# Final_circuit.net
KiCad netlist of a schematic drawn in EAGLE
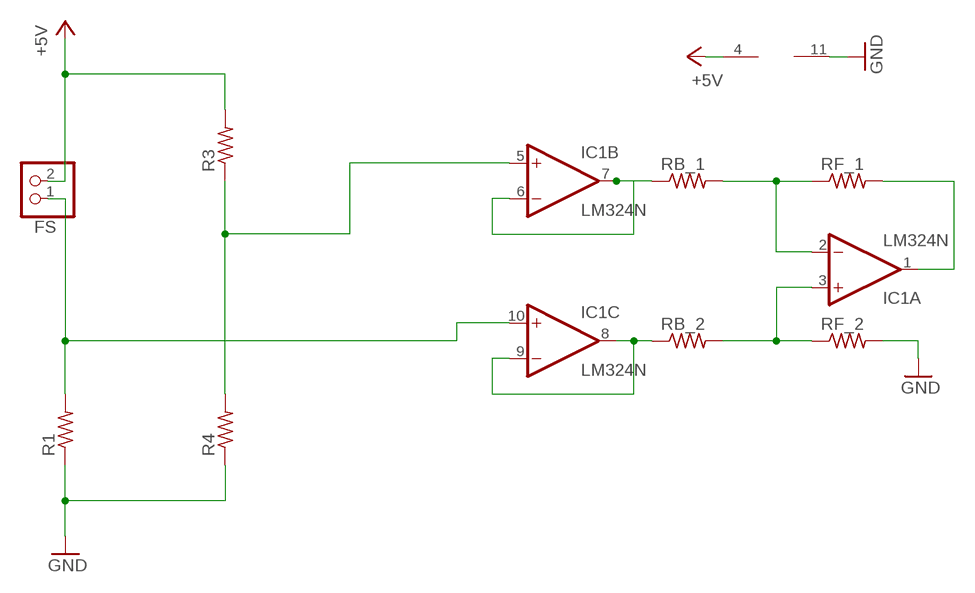
[diagram p0: schematic, sheet 1]

(export (version "E")
  (design (tool "Eeschema 10.0.6"))
  (components
    (comp (ref "FS")
      (value "PINHD-1X2")
      (footprint "eagle-import:1X02")
      (libsource (lib "eagle-import") (part "PINHD-1X2"))
    )
    (comp (ref "IC1")
      (value "LM324N")
      (footprint "eagle-import:DIL14")
      (libsource (lib "eagle-import") (part "LM324N"))
    )
    (comp (ref "R1")
      (value "R-US_0207/10")
      (footprint "eagle-import:0207_10")
      (libsource (lib "eagle-import") (part "R-US_0207/10"))
    )
    (comp (ref "R3")
      (value "R-US_0207/10")
      (footprint "eagle-import:0207_10")
      (libsource (lib "eagle-import") (part "R-US_0207/10"))
    )
    (comp (ref "R4")
      (value "R-US_0207/10")
      (footprint "eagle-import:0207_10")
      (libsource (lib "eagle-import") (part "R-US_0207/10"))
    )
    (comp (ref "RB_1")
      (value "R-US_0207/10")
      (footprint "eagle-import:0207_10")
      (libsource (lib "eagle-import") (part "R-US_0207/10"))
    )
    (comp (ref "RB_2")
      (value "R-US_0207/10")
      (footprint "eagle-import:0207_10")
      (libsource (lib "eagle-import") (part "R-US_0207/10"))
    )
    (comp (ref "RF_1")
      (value "R-US_0207/10")
      (footprint "eagle-import:0207_10")
      (libsource (lib "eagle-import") (part "R-US_0207/10"))
    )
    (comp (ref "RF_2")
      (value "R-US_0207/10")
      (footprint "eagle-import:0207_10")
      (libsource (lib "eagle-import") (part "R-US_0207/10"))
    )
  )
  (nets
    (net (code "1") (name "+5V") (class "Default")
      (node (ref "FS") (pin "2") (pinfunction "2_2") (pintype "passive"))
      (node (ref "IC1") (pin "4") (pinfunction "V+_4") (pintype "power_in"))
      (node (ref "R3") (pin "2") (pinfunction "2_2") (pintype "passive"))
    )
    (net (code "2") (name "GND") (class "Default")
      (node (ref "IC1") (pin "11") (pinfunction "V-_11") (pintype "power_in"))
      (node (ref "R1") (pin "1") (pinfunction "1_1") (pintype "passive"))
      (node (ref "R4") (pin "1") (pinfunction "1_1") (pintype "passive"))
      (node (ref "RF_2") (pin "2") (pinfunction "2_2") (pintype "passive"))
    )
    (net (code "3") (name "Net-(IC1A-+IN)") (class "Default")
      (node (ref "IC1") (pin "3") (pinfunction "+IN_3") (pintype "input"))
      (node (ref "RB_2") (pin "2") (pinfunction "2_2") (pintype "passive"))
      (node (ref "RF_2") (pin "1") (pinfunction "1_1") (pintype "passive"))
    )
    (net (code "4") (name "Net-(IC1A--IN)") (class "Default")
      (node (ref "IC1") (pin "2") (pinfunction "-IN_2") (pintype "input"))
      (node (ref "RB_1") (pin "2") (pinfunction "2_2") (pintype "passive"))
      (node (ref "RF_1") (pin "1") (pinfunction "1_1") (pintype "passive"))
    )
    (net (code "5") (name "Net-(IC1A-OUT)") (class "Default")
      (node (ref "IC1") (pin "1") (pinfunction "OUT_1") (pintype "output"))
      (node (ref "RF_1") (pin "2") (pinfunction "2_2") (pintype "passive"))
    )
    (net (code "6") (name "Net-(IC1B-+IN)") (class "Default")
      (node (ref "IC1") (pin "5") (pinfunction "+IN_5") (pintype "input"))
      (node (ref "R3") (pin "1") (pinfunction "1_1") (pintype "passive"))
      (node (ref "R4") (pin "2") (pinfunction "2_2") (pintype "passive"))
    )
    (net (code "7") (name "Net-(IC1B--IN)") (class "Default")
      (node (ref "IC1") (pin "6") (pinfunction "-IN_6") (pintype "input"))
      (node (ref "IC1") (pin "7") (pinfunction "OUT_7") (pintype "output"))
      (node (ref "RB_1") (pin "1") (pinfunction "1_1") (pintype "passive"))
    )
    (net (code "8") (name "Net-(IC1C-+IN)") (class "Default")
      (node (ref "FS") (pin "1") (pinfunction "1_1") (pintype "passive"))
      (node (ref "IC1") (pin "10") (pinfunction "+IN_10") (pintype "input"))
      (node (ref "R1") (pin "2") (pinfunction "2_2") (pintype "passive"))
    )
    (net (code "9") (name "Net-(IC1C--IN)") (class "Default")
      (node (ref "IC1") (pin "8") (pinfunction "OUT_8") (pintype "output"))
      (node (ref "IC1") (pin "9") (pinfunction "-IN_9") (pintype "input"))
      (node (ref "RB_2") (pin "1") (pinfunction "1_1") (pintype "passive"))
    )
  )
)
